# PIR_MOC_2.net
KiCad netlist of a schematic drawn in EAGLE
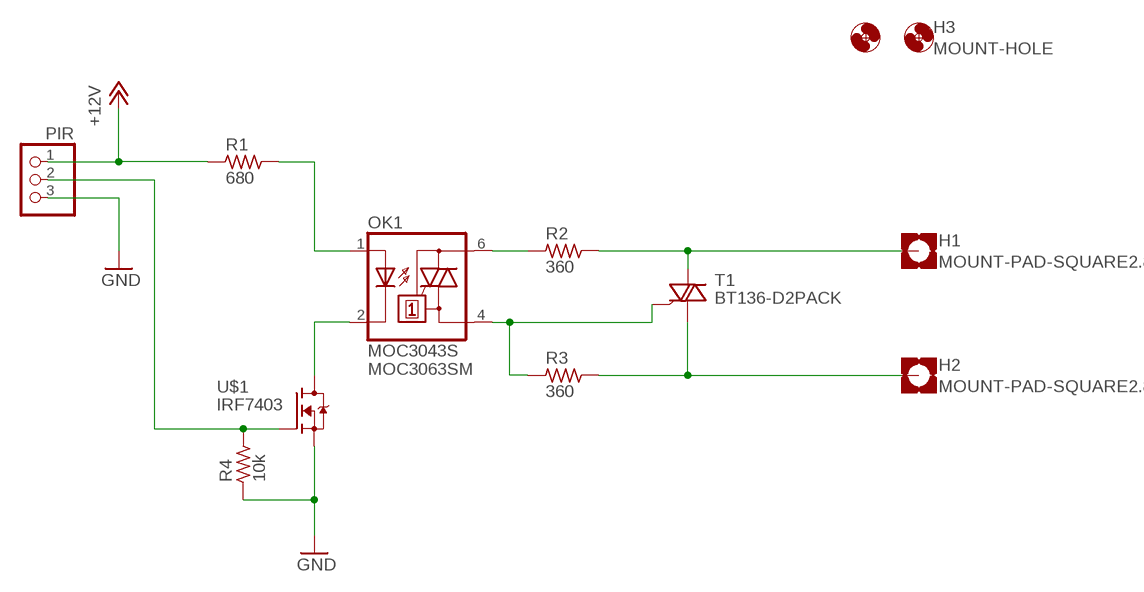
[diagram p0: schematic, sheet 1]

(export (version "E")
  (design (tool "Eeschema 10.0.6"))
  (components
    (comp (ref "H1")
      (value "MOUNT-PAD-SQUARE2.8")
      (footprint "eagle-import:2,8-PAD-SQUARE")
      (libsource (lib "eagle-import") (part "MOUNT-PAD-SQUARE2.8"))
    )
    (comp (ref "H2")
      (value "MOUNT-PAD-SQUARE2.8")
      (footprint "eagle-import:2,8-PAD-SQUARE")
      (libsource (lib "eagle-import") (part "MOUNT-PAD-SQUARE2.8"))
    )
    (comp (ref "H3")
      (value "MOUNT-HOLE")
      (footprint "eagle-import:CASE_20-31_VHOLES")
      (libsource (lib "eagle-import") (part "MOUNT-HOLE"))
    )
    (comp (ref "OK1")
      (value "MOC3043S")
      (footprint "eagle-import:DIL6-SMD")
      (fields
        (field (name "MF") "FAIRCHILD SEMICONDUCTOR")
        (field (name "MPN") "MOC3043SM")
        (field (name "MPN_1") "MOC3063SM")
      )
      (libsource (lib "eagle-import") (part "MOC30S43"))
    )
    (comp (ref "PIR")
      (value "PINHD-1X03_2.54-S")
      (footprint "eagle-import:1X03-S")
      (libsource (lib "eagle-import") (part "PINHD-1X03_2.54-S"))
    )
    (comp (ref "R1")
      (value "680")
      (footprint "eagle-import:R1206")
      (libsource (lib "eagle-import") (part "R_1206"))
    )
    (comp (ref "R2")
      (value "360")
      (footprint "eagle-import:R1206")
      (libsource (lib "eagle-import") (part "R_1206"))
    )
    (comp (ref "R3")
      (value "360")
      (footprint "eagle-import:R1206")
      (libsource (lib "eagle-import") (part "R_1206"))
    )
    (comp (ref "R4")
      (value "10k")
      (footprint "eagle-import:R1206")
      (libsource (lib "eagle-import") (part "R_1206"))
    )
    (comp (ref "T1")
      (value "BT136-D2PACK")
      (footprint "eagle-import:TO263")
      (libsource (lib "eagle-import") (part "BT136-D2PACK"))
    )
    (comp (ref "U$1")
      (value "IRF7403")
      (footprint "eagle-import:SO-8")
      (libsource (lib "eagle-import") (part "IRF7403"))
    )
  )
  (nets
    (net (code "1") (name "+12V") (class "Default")
      (node (ref "PIR") (pin "1") (pinfunction "1_1") (pintype "passive"))
      (node (ref "R1") (pin "1") (pinfunction "1_1") (pintype "passive"))
    )
    (net (code "2") (name "GND") (class "Default")
      (node (ref "PIR") (pin "3") (pinfunction "3_3") (pintype "passive"))
      (node (ref "R4") (pin "1") (pinfunction "1_1") (pintype "passive"))
      (node (ref "U$1") (pin "1") (pinfunction "S_1") (pintype "passive"))
      (node (ref "U$1") (pin "2") (pinfunction "S_2") (pintype "passive"))
      (node (ref "U$1") (pin "3") (pinfunction "S_3") (pintype "passive"))
    )
    (net (code "3") (name "Net-(H1-MOUNT)") (class "Default")
      (node (ref "H1") (pin "B2,8") (pinfunction "MOUNT_B2,8") (pintype "passive"))
      (node (ref "R2") (pin "2") (pinfunction "2_2") (pintype "passive"))
      (node (ref "T1") (pin "3") (pinfunction "A2_3") (pintype "passive"))
    )
    (net (code "4") (name "Net-(H2-MOUNT)") (class "Default")
      (node (ref "H2") (pin "B2,8") (pinfunction "MOUNT_B2,8") (pintype "passive"))
      (node (ref "R3") (pin "2") (pinfunction "2_2") (pintype "passive"))
      (node (ref "T1") (pin "1") (pinfunction "A1_1") (pintype "passive"))
    )
    (net (code "5") (name "Net-(OK1-A)") (class "Default")
      (node (ref "OK1") (pin "1") (pinfunction "A_1") (pintype "passive"))
      (node (ref "R1") (pin "2") (pinfunction "2_2") (pintype "passive"))
    )
    (net (code "6") (name "Net-(OK1-A1)") (class "Default")
      (node (ref "OK1") (pin "4") (pinfunction "A1_4") (pintype "passive"))
      (node (ref "R3") (pin "1") (pinfunction "1_1") (pintype "passive"))
      (node (ref "T1") (pin "2") (pinfunction "G_2") (pintype "passive"))
    )
    (net (code "7") (name "Net-(OK1-A2)") (class "Default")
      (node (ref "OK1") (pin "6") (pinfunction "A2_6") (pintype "passive"))
      (node (ref "R2") (pin "1") (pinfunction "1_1") (pintype "passive"))
    )
    (net (code "8") (name "Net-(OK1-C)") (class "Default")
      (node (ref "OK1") (pin "2") (pinfunction "C_2") (pintype "passive"))
      (node (ref "U$1") (pin "5") (pinfunction "D_5") (pintype "passive"))
      (node (ref "U$1") (pin "6") (pinfunction "D_6") (pintype "passive"))
      (node (ref "U$1") (pin "7") (pinfunction "D_7") (pintype "passive"))
      (node (ref "U$1") (pin "8") (pinfunction "D_8") (pintype "passive"))
    )
    (net (code "9") (name "Net-(U$1-G)") (class "Default")
      (node (ref "PIR") (pin "2") (pinfunction "2_2") (pintype "passive"))
      (node (ref "R4") (pin "2") (pinfunction "2_2") (pintype "passive"))
      (node (ref "U$1") (pin "4") (pinfunction "G_4") (pintype "passive"))
    )
  )
)
